# Sheet1.net
KiCad netlist of a schematic drawn in Altium Designer
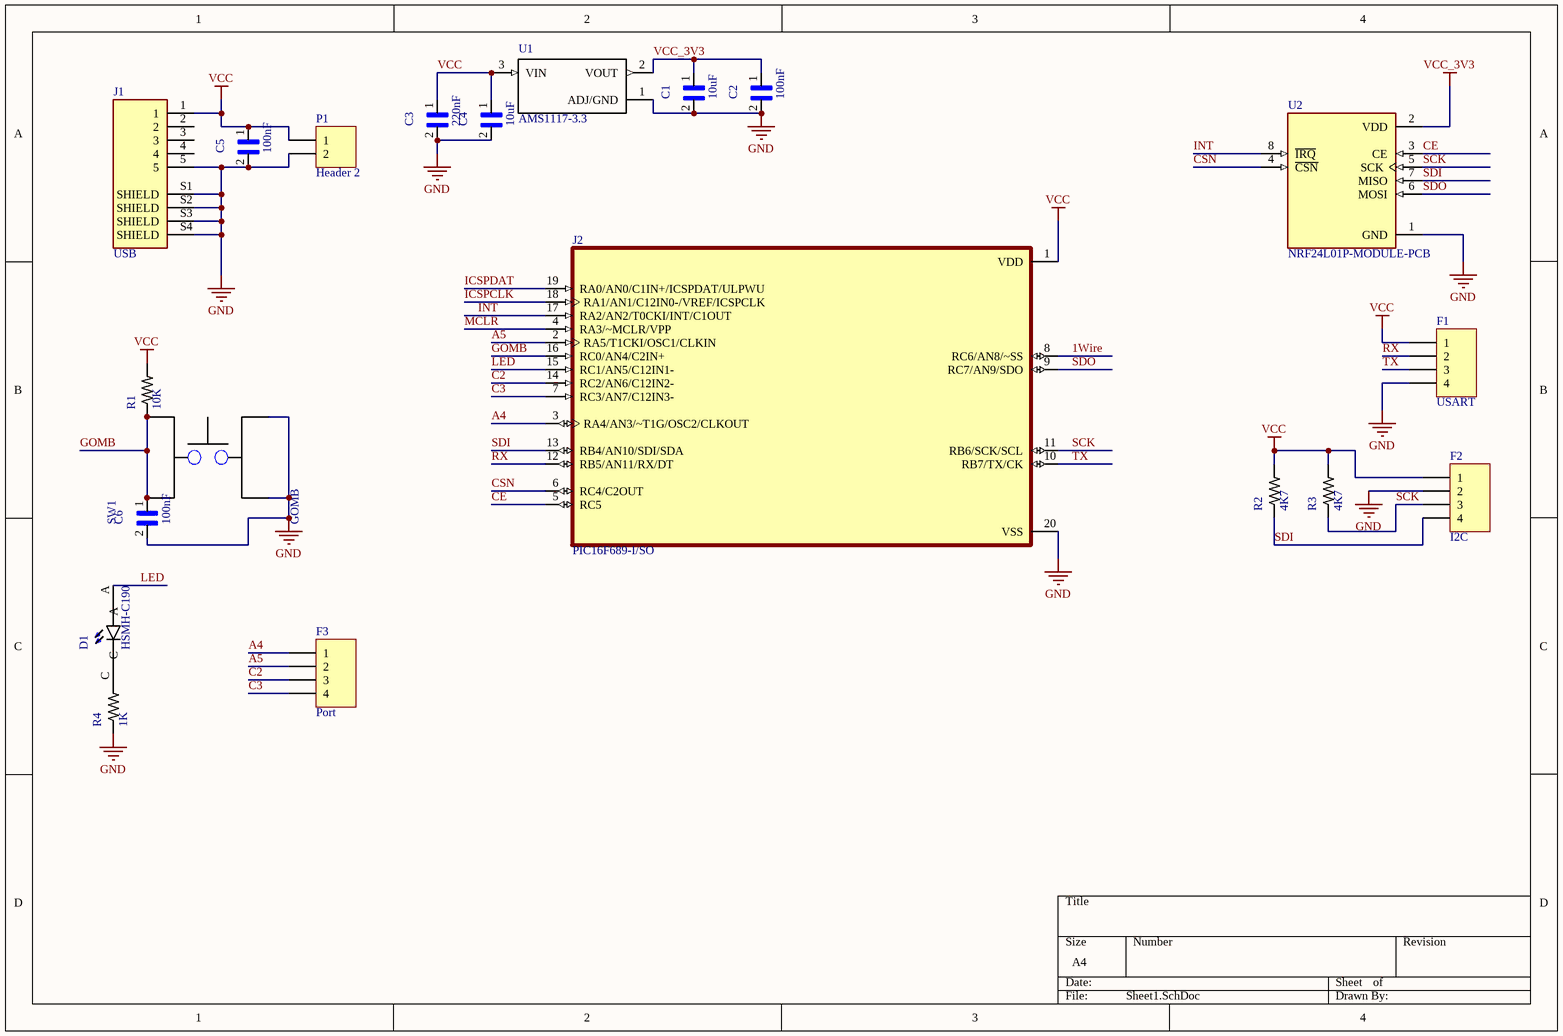
[diagram p0: Sheet1.SchDoc]

(export (version "E")
  (design (tool "Eeschema 10.0.6"))
  (components
    (comp (ref "C1")
      (value "10uF")
      (footprint "CAP0603")
      (description "Cap Ceramic")
      (fields (field (name "MF") "AVX") (field (name "MP") "06031A6R0BAT4A"))
      (libsource (lib "Peti") (part "0603"))
    )
    (comp (ref "C2")
      (value "100nF")
      (footprint "CAP0603")
      (description "Cap Ceramic")
      (fields (field (name "MF") "AVX") (field (name "MP") "06031A6R0BAT4A"))
      (libsource (lib "Peti") (part "0603"))
    )
    (comp (ref "C3")
      (value "220nF")
      (footprint "CAP0603")
      (description "Cap Ceramic")
      (fields (field (name "MF") "AVX") (field (name "MP") "06031A6R0BAT4A"))
      (libsource (lib "Peti") (part "0603"))
    )
    (comp (ref "C4")
      (value "10uF")
      (footprint "CAP0603")
      (description "Cap Ceramic")
      (fields (field (name "MF") "AVX") (field (name "MP") "06031A6R0BAT4A"))
      (libsource (lib "Peti") (part "0603"))
    )
    (comp (ref "C5")
      (value "100nF")
      (footprint "CAP0603")
      (description "Cap Ceramic")
      (fields (field (name "MF") "AVX") (field (name "MP") "06031A6R0BAT4A"))
      (libsource (lib "Peti") (part "0603"))
    )
    (comp (ref "C6")
      (value "100nF")
      (footprint "CAP0603")
      (description "Cap Ceramic")
      (fields (field (name "MF") "AVX") (field (name "MP") "06031A6R0BAT4A"))
      (libsource (lib "Peti") (part "0603"))
    )
    (comp (ref "D1")
      (value "HSMH-C190")
      (footprint "LEDM1608X80_HSMH-C190(Primary)")
      (description "LED; SMD; 0603; red; 7.2-17mcd; 1.6x0.8mm; 170Â°; 1.8Ă·2.6V; 20mA")
      (fields (field (name "MF") "Broadcom Limited"))
      (libsource (lib "Peti") (part "HSMH-C190"))
    )
    (comp (ref "F1")
      (value "USART")
      (footprint "HDR1X4")
      (description "Header, 4-Pin")
      (fields (field (name "PUBLISHER") "Altium Limited"))
      (libsource (lib "Miscellaneous Connectors") (part "Header 4"))
    )
    (comp (ref "F2")
      (value "I2C")
      (footprint "HDR1X4")
      (description "Header, 4-Pin")
      (fields (field (name "PUBLISHER") "Altium Limited"))
      (libsource (lib "Miscellaneous Connectors") (part "Header 4"))
    )
    (comp (ref "F3")
      (value "Port")
      (footprint "HDR1X4")
      (description "Header, 4-Pin")
      (fields (field (name "PUBLISHER") "Altium Limited"))
      (libsource (lib "Miscellaneous Connectors") (part "Header 4"))
    )
    (comp (ref "J1")
      (value "USB")
      (footprint "MicroUSB:WE_629105136821")
      (description "USB - micro B USB 2.0 Receptacle Connector 5 Position Surface Mount, Right Angle")
      (fields (field (name "MF") "Wurth Electronics") (field (name "MP") "629105136821"))
      (libsource (lib "629105136821") (part "629105136821"))
    )
    (comp (ref "J2")
      (value "PIC16F689-I/SO")
      (footprint "SOIC127P1032X265-20N:SOIC127P1032X265-20N")
      (libsource (lib "PIC16F689-I_SO") (part "PIC16F689-I/SO"))
    )
    (comp (ref "P1")
      (value "Header 2")
      (footprint "HDR1X2")
      (description "Header, 2-Pin")
      (fields (field (name "PUBLISHER") "Altium Limited"))
      (libsource (lib "Miscellaneous Connectors") (part "Header 2"))
    )
    (comp (ref "R1")
      (value "10K")
      (footprint "RES0603")
      (description "0603RES")
      (fields (field (name "MF") "Panasonic") (field (name "MP") "EXB-34V103JV"))
      (libsource (lib "Peti") (part "0603RES"))
    )
    (comp (ref "R2")
      (value "4K7")
      (footprint "RES0603")
      (description "0603RES")
      (fields (field (name "MF") "Panasonic") (field (name "MP") "EXB-34V103JV"))
      (libsource (lib "Peti") (part "0603RES"))
    )
    (comp (ref "R3")
      (value "4K7")
      (footprint "RES0603")
      (description "0603RES")
      (fields (field (name "MF") "Panasonic") (field (name "MP") "EXB-34V103JV"))
      (libsource (lib "Peti") (part "0603RES"))
    )
    (comp (ref "R4")
      (value "1K")
      (footprint "RES0603")
      (description "0603RES")
      (fields (field (name "MF") "Panasonic") (field (name "MP") "EXB-34V103JV"))
      (libsource (lib "Peti") (part "0603RES"))
    )
    (comp (ref "SW1")
      (value "GOMB")
      (footprint "SW_TL3342F160QG/TR")
      (description "Switch Tactile Spst-No 0.05a 12v")
      (fields (field (name "MP") "TL3342F160QG/TR") (field (name "MF") "E-Switch"))
      (libsource (lib "Peti") (part "TL3342F160QG/TR"))
    )
    (comp (ref "U1")
      (value "AMS1117-3.3")
      (footprint "SOT229P700X180-4N")
      (description "Sot223/Pkg 1-Amp 3.3-Volt Low Drop Out Voltage Regulatator")
      (fields (field (name "MF") "Advanced Monolithic Systems"))
      (libsource (lib "Peti") (part "AMS1117-3.3"))
    )
    (comp (ref "U2")
      (value "NRF24L01P-MODULE-PCB")
      (footprint "XCVR_NRF24L01P-MODULE-PCB:XCVR_NRF24L01P-MODULE-PCB")
      (description "- Transceiver For Use With nRF24L01+")
      (fields (field (name "MF") "Nordic Semiconductor"))
      (libsource (lib "NRF24L01P-MODULE-PCB") (part "NRF24L01P-MODULE-PCB"))
    )
  )
  (nets
    (net (code "1") (name "/1Wire") (class "Default")
      (node (ref "J2") (pin "8") (pinfunction "RC6/AN8/~SS_8") (pintype "bidirectional"))
    )
    (net (code "2") (name "/A4") (class "Default")
      (node (ref "F3") (pin "1") (pinfunction "1_1") (pintype "passive"))
      (node (ref "J2") (pin "3") (pinfunction "RA4/AN3/~T1G/OSC2/CLKOUT_3") (pintype "bidirectional"))
    )
    (net (code "3") (name "/A5") (class "Default")
      (node (ref "F3") (pin "2") (pinfunction "2_2") (pintype "passive"))
      (node (ref "J2") (pin "2") (pinfunction "RA5/T1CKI/OSC1/CLKIN_2") (pintype "input"))
    )
    (net (code "4") (name "/C2") (class "Default")
      (node (ref "F3") (pin "3") (pinfunction "3_3") (pintype "passive"))
      (node (ref "J2") (pin "14") (pinfunction "RC2/AN6/C12IN2-_14") (pintype "input"))
    )
    (net (code "5") (name "/C3") (class "Default")
      (node (ref "F3") (pin "4") (pinfunction "4_4") (pintype "passive"))
      (node (ref "J2") (pin "7") (pinfunction "RC3/AN7/C12IN3-_7") (pintype "input"))
    )
    (net (code "6") (name "/CE") (class "Default")
      (node (ref "J2") (pin "5") (pinfunction "RC5_5") (pintype "bidirectional"))
      (node (ref "U2") (pin "3") (pinfunction "CE_3") (pintype "input"))
    )
    (net (code "7") (name "/CSN") (class "Default")
      (node (ref "J2") (pin "6") (pinfunction "RC4/C2OUT_6") (pintype "bidirectional"))
      (node (ref "U2") (pin "4") (pinfunction "~{CSN}_4") (pintype "input"))
    )
    (net (code "8") (name "/GOMB") (class "Default")
      (node (ref "C6") (pin "1") (pinfunction "1_1") (pintype "passive"))
      (node (ref "J2") (pin "16") (pinfunction "RC0/AN4/C2IN+_16") (pintype "input"))
      (node (ref "R1") (pin "1") (pinfunction "1_1") (pintype "passive"))
      (node (ref "SW1") (pin "3") (pinfunction "3_3") (pintype "passive"))
      (node (ref "SW1") (pin "4") (pinfunction "4_4") (pintype "passive"))
    )
    (net (code "9") (name "/ICSPCLK") (class "Default")
      (node (ref "J2") (pin "18") (pinfunction "RA1/AN1/C12IN0-/VREF/ICSPCLK_18") (pintype "input"))
    )
    (net (code "10") (name "/ICSPDAT") (class "Default")
      (node (ref "J2") (pin "19") (pinfunction "RA0/AN0/C1IN+/ICSPDAT/ULPWU_19") (pintype "input"))
    )
    (net (code "11") (name "/INT") (class "Default")
      (node (ref "J2") (pin "17") (pinfunction "RA2/AN2/T0CKI/INT/C1OUT_17") (pintype "input"))
      (node (ref "U2") (pin "8") (pinfunction "~{IRQ}_8") (pintype "input"))
    )
    (net (code "12") (name "/LED") (class "Default")
      (node (ref "D1") (pin "A") (pinfunction "A_A") (pintype "passive"))
      (node (ref "J2") (pin "15") (pinfunction "RC1/AN5/C12IN1-_15") (pintype "input"))
    )
    (net (code "13") (name "/MCLR") (class "Default")
      (node (ref "J2") (pin "4") (pinfunction "RA3/~MCLR/VPP_4") (pintype "input"))
    )
    (net (code "14") (name "/RX") (class "Default")
      (node (ref "F1") (pin "2") (pinfunction "2_2") (pintype "passive"))
      (node (ref "J2") (pin "12") (pinfunction "RB5/AN11/RX/DT_12") (pintype "bidirectional"))
    )
    (net (code "15") (name "/SCK") (class "Default")
      (node (ref "F2") (pin "3") (pinfunction "3_3") (pintype "passive"))
      (node (ref "J2") (pin "11") (pinfunction "RB6/SCK/SCL_11") (pintype "bidirectional"))
      (node (ref "R3") (pin "1") (pinfunction "1_1") (pintype "passive"))
      (node (ref "U2") (pin "5") (pinfunction "SCK_5") (pintype "input"))
    )
    (net (code "16") (name "/SDI") (class "Default")
      (node (ref "F2") (pin "4") (pinfunction "4_4") (pintype "passive"))
      (node (ref "J2") (pin "13") (pinfunction "RB4/AN10/SDI/SDA_13") (pintype "bidirectional"))
      (node (ref "R2") (pin "1") (pinfunction "1_1") (pintype "passive"))
      (node (ref "U2") (pin "7") (pinfunction "MISO_7") (pintype "input"))
    )
    (net (code "17") (name "/SDO") (class "Default")
      (node (ref "J2") (pin "9") (pinfunction "RC7/AN9/SDO_9") (pintype "bidirectional"))
      (node (ref "U2") (pin "6") (pinfunction "MOSI_6") (pintype "input"))
    )
    (net (code "18") (name "/TX") (class "Default")
      (node (ref "F1") (pin "3") (pinfunction "3_3") (pintype "passive"))
      (node (ref "J2") (pin "10") (pinfunction "RB7/TX/CK_10") (pintype "bidirectional"))
    )
    (net (code "19") (name "GND") (class "Default")
      (node (ref "C1") (pin "2") (pinfunction "2_2") (pintype "passive"))
      (node (ref "C2") (pin "2") (pinfunction "2_2") (pintype "passive"))
      (node (ref "C3") (pin "2") (pinfunction "2_2") (pintype "passive"))
      (node (ref "C4") (pin "2") (pinfunction "2_2") (pintype "passive"))
      (node (ref "C5") (pin "2") (pinfunction "2_2") (pintype "passive"))
      (node (ref "C6") (pin "2") (pinfunction "2_2") (pintype "passive"))
      (node (ref "F1") (pin "4") (pinfunction "4_4") (pintype "passive"))
      (node (ref "F2") (pin "2") (pinfunction "2_2") (pintype "passive"))
      (node (ref "J1") (pin "5") (pinfunction "5_5") (pintype "passive"))
      (node (ref "J1") (pin "S1") (pinfunction "SHIELD_S1") (pintype "passive"))
      (node (ref "J1") (pin "S2") (pinfunction "SHIELD_S2") (pintype "passive"))
      (node (ref "J1") (pin "S3") (pinfunction "SHIELD_S3") (pintype "passive"))
      (node (ref "J1") (pin "S4") (pinfunction "SHIELD_S4") (pintype "passive"))
      (node (ref "J2") (pin "20") (pinfunction "VSS_20") (pintype "power_in"))
      (node (ref "P1") (pin "2") (pinfunction "2_2") (pintype "passive"))
      (node (ref "R4") (pin "1") (pinfunction "1_1") (pintype "passive"))
      (node (ref "SW1") (pin "1") (pinfunction "1_1") (pintype "passive"))
      (node (ref "SW1") (pin "2") (pinfunction "2_2") (pintype "passive"))
      (node (ref "U1") (pin "1") (pinfunction "ADJ/GND_1") (pintype "power_in"))
      (node (ref "U2") (pin "1") (pinfunction "GND_1") (pintype "power_in"))
    )
    (net (code "20") (name "Net-(D1-PadC)") (class "Default")
      (node (ref "D1") (pin "C") (pinfunction "C_C") (pintype "passive"))
      (node (ref "R4") (pin "2") (pinfunction "2_2") (pintype "passive"))
    )
    (net (code "21") (name "VCC") (class "Default")
      (node (ref "C3") (pin "1") (pinfunction "1_1") (pintype "passive"))
      (node (ref "C4") (pin "1") (pinfunction "1_1") (pintype "passive"))
      (node (ref "C5") (pin "1") (pinfunction "1_1") (pintype "passive"))
      (node (ref "F1") (pin "1") (pinfunction "1_1") (pintype "passive"))
      (node (ref "F2") (pin "1") (pinfunction "1_1") (pintype "passive"))
      (node (ref "J1") (pin "1") (pinfunction "1_1") (pintype "passive"))
      (node (ref "J2") (pin "1") (pinfunction "VDD_1") (pintype "power_in"))
      (node (ref "P1") (pin "1") (pinfunction "1_1") (pintype "passive"))
      (node (ref "R1") (pin "2") (pinfunction "2_2") (pintype "passive"))
      (node (ref "R2") (pin "2") (pinfunction "2_2") (pintype "passive"))
      (node (ref "R3") (pin "2") (pinfunction "2_2") (pintype "passive"))
      (node (ref "U1") (pin "3") (pinfunction "VIN_3") (pintype "input"))
    )
    (net (code "22") (name "VCC_3V3") (class "Default")
      (node (ref "C1") (pin "1") (pinfunction "1_1") (pintype "passive"))
      (node (ref "C2") (pin "1") (pinfunction "1_1") (pintype "passive"))
      (node (ref "U1") (pin "2") (pinfunction "VOUT_2") (pintype "output"))
      (node (ref "U2") (pin "2") (pinfunction "VDD_2") (pintype "power_in"))
    )
    (net (code "23") (name "unconnected-(J1-Pad2)") (class "Default")
      (node (ref "J1") (pin "2") (pinfunction "2_2") (pintype "passive"))
    )
    (net (code "24") (name "unconnected-(J1-Pad3)") (class "Default")
      (node (ref "J1") (pin "3") (pinfunction "3_3") (pintype "passive"))
    )
    (net (code "25") (name "unconnected-(J1-Pad4)") (class "Default")
      (node (ref "J1") (pin "4") (pinfunction "4_4") (pintype "passive"))
    )
  )
)
